# alimV1.net
KiCad netlist of a schematic drawn in EAGLE
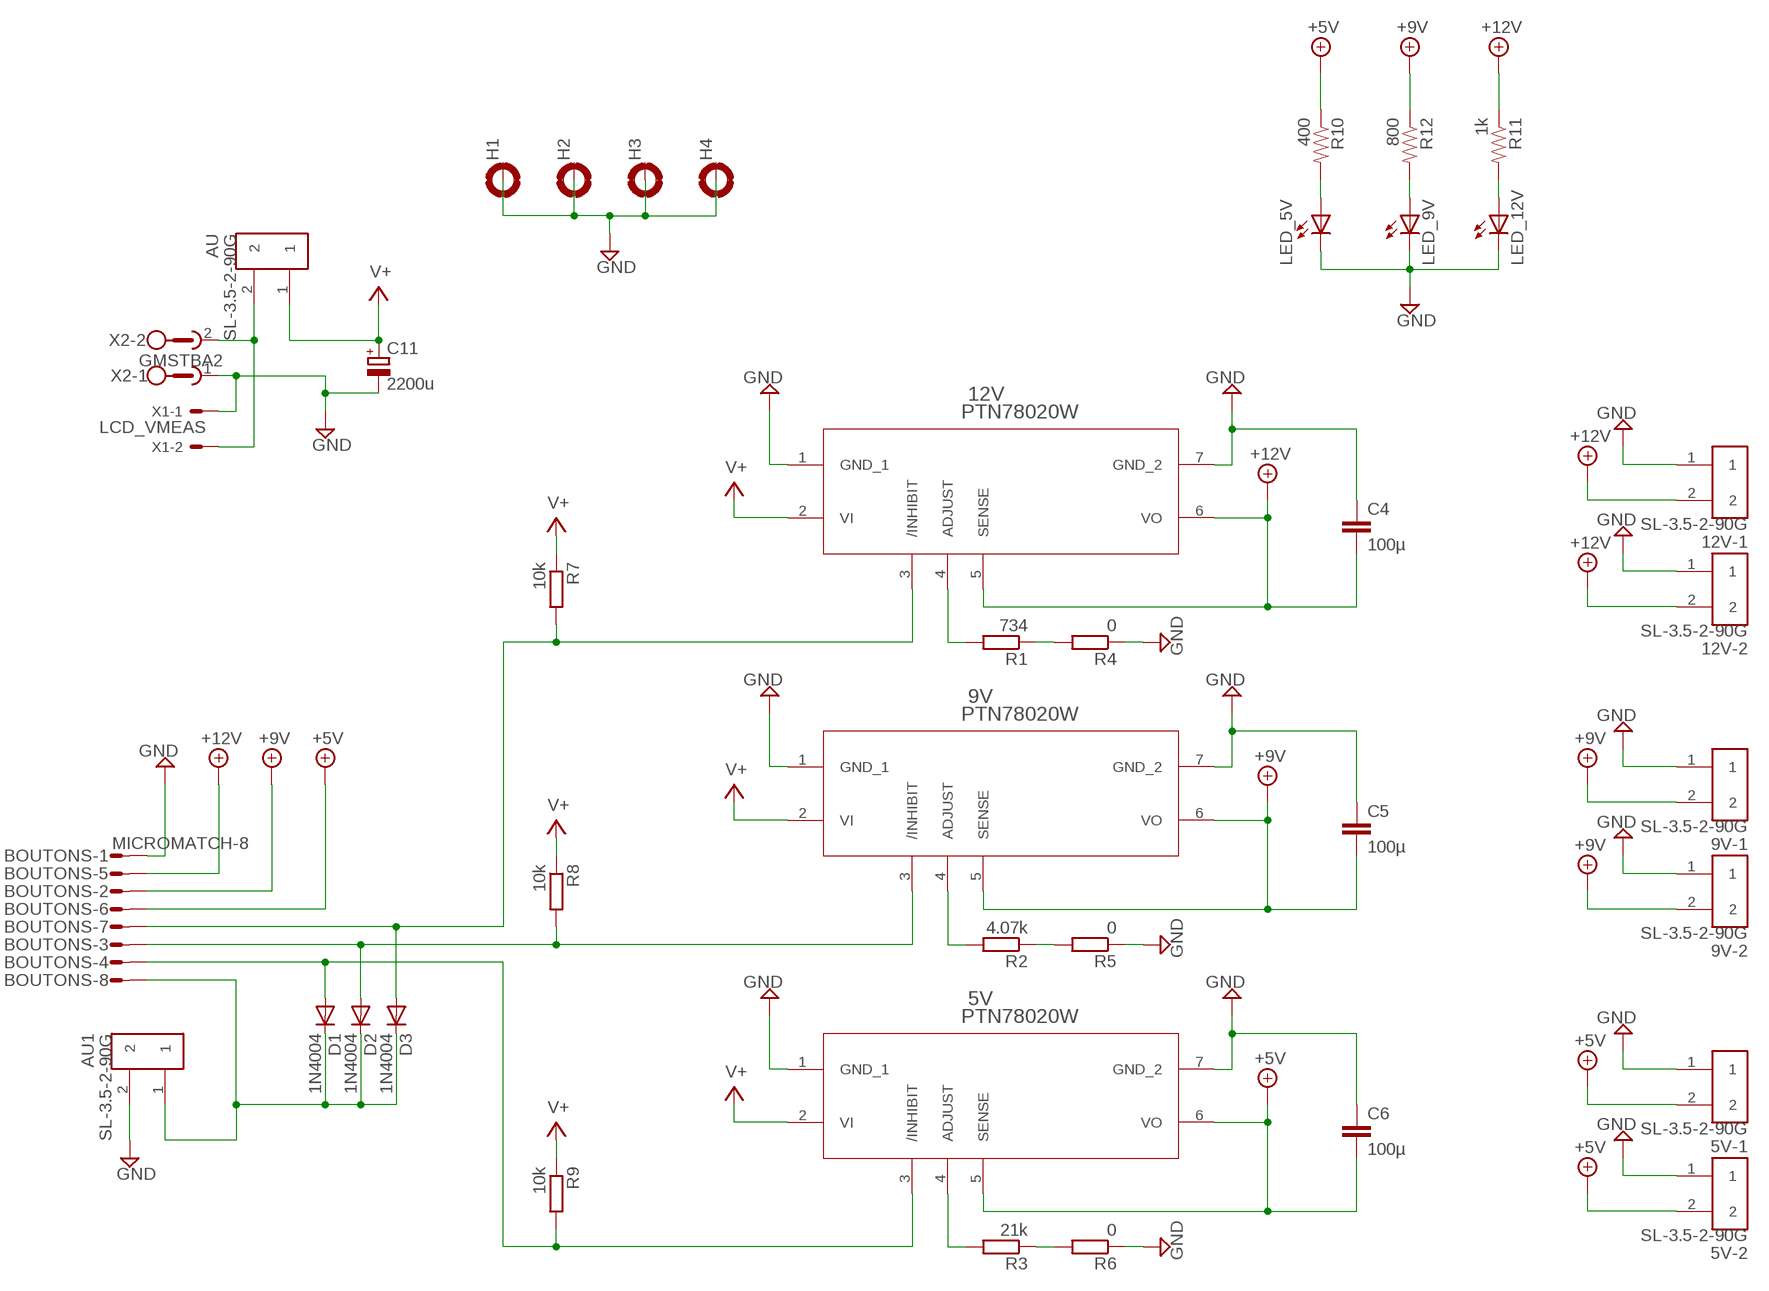
[diagram p0: schematic, sheet 1]

(export (version "E")
  (design (tool "Eeschema 10.0.6"))
  (components
    (comp (ref "5V")
      (value "PTN78020W")
      (footprint "eagle-import:EUK7")
      (libsource (lib "eagle-import") (part "PTN78020W"))
    )
    (comp (ref "5V-1")
      (value "SL-3.5-2-90G")
      (footprint "eagle-import:SL-3.5-2-90G")
      (libsource (lib "eagle-import") (part "SL-3.5-2-90G"))
    )
    (comp (ref "5V-2")
      (value "SL-3.5-2-90G")
      (footprint "eagle-import:SL-3.5-2-90G")
      (libsource (lib "eagle-import") (part "SL-3.5-2-90G"))
    )
    (comp (ref "9V")
      (value "PTN78020W")
      (footprint "eagle-import:EUK7")
      (libsource (lib "eagle-import") (part "PTN78020W"))
    )
    (comp (ref "9V-1")
      (value "SL-3.5-2-90G")
      (footprint "eagle-import:SL-3.5-2-90G")
      (libsource (lib "eagle-import") (part "SL-3.5-2-90G"))
    )
    (comp (ref "9V-2")
      (value "SL-3.5-2-90G")
      (footprint "eagle-import:SL-3.5-2-90G")
      (libsource (lib "eagle-import") (part "SL-3.5-2-90G"))
    )
    (comp (ref "12V")
      (value "PTN78020W")
      (footprint "eagle-import:EUK7")
      (libsource (lib "eagle-import") (part "PTN78020W"))
    )
    (comp (ref "12V-1")
      (value "SL-3.5-2-90G")
      (footprint "eagle-import:SL-3.5-2-90G")
      (libsource (lib "eagle-import") (part "SL-3.5-2-90G"))
    )
    (comp (ref "12V-2")
      (value "SL-3.5-2-90G")
      (footprint "eagle-import:SL-3.5-2-90G")
      (libsource (lib "eagle-import") (part "SL-3.5-2-90G"))
    )
    (comp (ref "AU")
      (value "SL-3.5-2-90G")
      (footprint "eagle-import:SL-3.5-2-90G")
      (libsource (lib "eagle-import") (part "SL-3.5-2-90G"))
    )
    (comp (ref "AU1")
      (value "SL-3.5-2-90G")
      (footprint "eagle-import:SL-3.5-2-90G")
      (libsource (lib "eagle-import") (part "SL-3.5-2-90G"))
    )
    (comp (ref "BOUTONS")
      (value "MICROMATCH-8")
      (footprint "eagle-import:MICROMATCH-8")
      (fields (field (name "MF") "FARNELL") (field (name "MPN") "7-215464-8"))
      (libsource (lib "eagle-import") (part "MICROMATCH-8"))
    )
    (comp (ref "C4")
      (value "100µ")
      (footprint "eagle-import:C025-025X050")
      (libsource (lib "eagle-import") (part "C-EU025-025X050"))
    )
    (comp (ref "C5")
      (value "100µ")
      (footprint "eagle-import:C025-025X050")
      (libsource (lib "eagle-import") (part "C-EU025-025X050"))
    )
    (comp (ref "C6")
      (value "100µ")
      (footprint "eagle-import:C025-025X050")
      (libsource (lib "eagle-import") (part "C-EU025-025X050"))
    )
    (comp (ref "C11")
      (value "2200u")
      (footprint "eagle-import:TT5D11")
      (libsource (lib "eagle-import") (part "CPOL-EUTT5D11"))
    )
    (comp (ref "D1")
      (value "1N4004")
      (footprint "eagle-import:DO41-10")
      (libsource (lib "eagle-import") (part "1N4004"))
    )
    (comp (ref "D2")
      (value "1N4004")
      (footprint "eagle-import:DO41-10")
      (libsource (lib "eagle-import") (part "1N4004"))
    )
    (comp (ref "D3")
      (value "1N4004")
      (footprint "eagle-import:DO41-10")
      (libsource (lib "eagle-import") (part "1N4004"))
    )
    (comp (ref "H1")
      (value "MOUNT-PAD-ROUND3.2")
      (footprint "eagle-import:3,2-PAD")
      (libsource (lib "eagle-import") (part "MOUNT-PAD-ROUND3.2"))
    )
    (comp (ref "H2")
      (value "MOUNT-PAD-ROUND3.2")
      (footprint "eagle-import:3,2-PAD")
      (libsource (lib "eagle-import") (part "MOUNT-PAD-ROUND3.2"))
    )
    (comp (ref "H3")
      (value "MOUNT-PAD-ROUND3.2")
      (footprint "eagle-import:3,2-PAD")
      (libsource (lib "eagle-import") (part "MOUNT-PAD-ROUND3.2"))
    )
    (comp (ref "H4")
      (value "MOUNT-PAD-ROUND3.2")
      (footprint "eagle-import:3,2-PAD")
      (libsource (lib "eagle-import") (part "MOUNT-PAD-ROUND3.2"))
    )
    (comp (ref "LED_5V")
      (value "LEDCHIPLED_0805")
      (footprint "eagle-import:CHIPLED_0805")
      (libsource (lib "eagle-import") (part "LEDCHIPLED_0805"))
    )
    (comp (ref "LED_9V")
      (value "LEDCHIPLED_0805")
      (footprint "eagle-import:CHIPLED_0805")
      (libsource (lib "eagle-import") (part "LEDCHIPLED_0805"))
    )
    (comp (ref "LED_12V")
      (value "LEDCHIPLED_0805")
      (footprint "eagle-import:CHIPLED_0805")
      (libsource (lib "eagle-import") (part "LEDCHIPLED_0805"))
    )
    (comp (ref "R1")
      (value "734")
      (footprint "eagle-import:R0805")
      (libsource (lib "eagle-import") (part "R-EU_R0805"))
    )
    (comp (ref "R2")
      (value "4.07k")
      (footprint "eagle-import:R0805")
      (libsource (lib "eagle-import") (part "R-EU_R0805"))
    )
    (comp (ref "R3")
      (value "21k")
      (footprint "eagle-import:R0805")
      (libsource (lib "eagle-import") (part "R-EU_R0805"))
    )
    (comp (ref "R4")
      (value "0")
      (footprint "eagle-import:R0805")
      (libsource (lib "eagle-import") (part "R-EU_R0805"))
    )
    (comp (ref "R5")
      (value "0")
      (footprint "eagle-import:R0805")
      (libsource (lib "eagle-import") (part "R-EU_R0805"))
    )
    (comp (ref "R6")
      (value "0")
      (footprint "eagle-import:R0805")
      (libsource (lib "eagle-import") (part "R-EU_R0805"))
    )
    (comp (ref "R7")
      (value "10k")
      (footprint "eagle-import:R0805")
      (libsource (lib "eagle-import") (part "R-EU_R0805"))
    )
    (comp (ref "R8")
      (value "10k")
      (footprint "eagle-import:R0805")
      (libsource (lib "eagle-import") (part "R-EU_R0805"))
    )
    (comp (ref "R9")
      (value "10k")
      (footprint "eagle-import:R0805")
      (libsource (lib "eagle-import") (part "R-EU_R0805"))
    )
    (comp (ref "R10")
      (value "400")
      (footprint "eagle-import:0805")
      (libsource (lib "eagle-import") (part "RESISTOR0805-RES"))
    )
    (comp (ref "R11")
      (value "1k")
      (footprint "eagle-import:0805")
      (libsource (lib "eagle-import") (part "RESISTOR0805-RES"))
    )
    (comp (ref "R12")
      (value "800")
      (footprint "eagle-import:0805")
      (libsource (lib "eagle-import") (part "RESISTOR0805-RES"))
    )
    (comp (ref "X1")
      (value "LCD_VMEAS")
      (footprint "eagle-import:22-23-2021")
      (fields (field (name "MF") "MOLEX") (field (name "MPN") "22-23-2021"))
      (libsource (lib "eagle-import") (part "22-23-2021"))
    )
    (comp (ref "X2")
      (value "GMSTBA2")
      (footprint "eagle-import:GMSTBA2")
      (fields (field (name "MF") "FARNELL") (field (name "MPN") "1757242"))
      (libsource (lib "eagle-import") (part "GMSTBA2"))
    )
  )
  (nets
    (net (code "1") (name "+5V") (class "Default")
      (node (ref "5V") (pin "5") (pinfunction "SENSE_5") (pintype "passive"))
      (node (ref "5V") (pin "6") (pinfunction "VO_6") (pintype "passive"))
      (node (ref "5V-1") (pin "2") (pinfunction "2_2") (pintype "bidirectional"))
      (node (ref "5V-2") (pin "2") (pinfunction "2_2") (pintype "bidirectional"))
      (node (ref "BOUTONS") (pin "6") (pinfunction "S_6") (pintype "passive"))
      (node (ref "C6") (pin "2") (pinfunction "2_2") (pintype "passive"))
      (node (ref "R10") (pin "1") (pinfunction "1_1") (pintype "passive"))
    )
    (net (code "2") (name "+9V") (class "Default")
      (node (ref "9V") (pin "5") (pinfunction "SENSE_5") (pintype "passive"))
      (node (ref "9V") (pin "6") (pinfunction "VO_6") (pintype "passive"))
      (node (ref "9V-1") (pin "2") (pinfunction "2_2") (pintype "bidirectional"))
      (node (ref "9V-2") (pin "2") (pinfunction "2_2") (pintype "bidirectional"))
      (node (ref "BOUTONS") (pin "2") (pinfunction "S_2") (pintype "passive"))
      (node (ref "C5") (pin "2") (pinfunction "2_2") (pintype "passive"))
      (node (ref "R12") (pin "1") (pinfunction "1_1") (pintype "passive"))
    )
    (net (code "3") (name "+12V") (class "Default")
      (node (ref "12V") (pin "5") (pinfunction "SENSE_5") (pintype "passive"))
      (node (ref "12V") (pin "6") (pinfunction "VO_6") (pintype "passive"))
      (node (ref "12V-1") (pin "2") (pinfunction "2_2") (pintype "bidirectional"))
      (node (ref "12V-2") (pin "2") (pinfunction "2_2") (pintype "bidirectional"))
      (node (ref "BOUTONS") (pin "5") (pinfunction "S_5") (pintype "passive"))
      (node (ref "C4") (pin "2") (pinfunction "2_2") (pintype "passive"))
      (node (ref "R11") (pin "1") (pinfunction "1_1") (pintype "passive"))
    )
    (net (code "4") (name "GND") (class "Default")
      (node (ref "12V") (pin "1") (pinfunction "GND_1_1") (pintype "passive"))
      (node (ref "12V") (pin "7") (pinfunction "GND_2_7") (pintype "passive"))
      (node (ref "12V-1") (pin "1") (pinfunction "1_1") (pintype "bidirectional"))
      (node (ref "12V-2") (pin "1") (pinfunction "1_1") (pintype "bidirectional"))
      (node (ref "5V") (pin "1") (pinfunction "GND_1_1") (pintype "passive"))
      (node (ref "5V") (pin "7") (pinfunction "GND_2_7") (pintype "passive"))
      (node (ref "5V-1") (pin "1") (pinfunction "1_1") (pintype "bidirectional"))
      (node (ref "5V-2") (pin "1") (pinfunction "1_1") (pintype "bidirectional"))
      (node (ref "9V") (pin "1") (pinfunction "GND_1_1") (pintype "passive"))
      (node (ref "9V") (pin "7") (pinfunction "GND_2_7") (pintype "passive"))
      (node (ref "9V-1") (pin "1") (pinfunction "1_1") (pintype "bidirectional"))
      (node (ref "9V-2") (pin "1") (pinfunction "1_1") (pintype "bidirectional"))
      (node (ref "AU1") (pin "2") (pinfunction "2_2") (pintype "bidirectional"))
      (node (ref "BOUTONS") (pin "1") (pinfunction "S_1") (pintype "passive"))
      (node (ref "C11") (pin "-") (pinfunction "-_-") (pintype "passive"))
      (node (ref "C4") (pin "1") (pinfunction "1_1") (pintype "passive"))
      (node (ref "C5") (pin "1") (pinfunction "1_1") (pintype "passive"))
      (node (ref "C6") (pin "1") (pinfunction "1_1") (pintype "passive"))
      (node (ref "H1") (pin "B3,2") (pinfunction "MOUNT_B3,2") (pintype "passive"))
      (node (ref "H2") (pin "B3,2") (pinfunction "MOUNT_B3,2") (pintype "passive"))
      (node (ref "H3") (pin "B3,2") (pinfunction "MOUNT_B3,2") (pintype "passive"))
      (node (ref "H4") (pin "B3,2") (pinfunction "MOUNT_B3,2") (pintype "passive"))
      (node (ref "LED_12V") (pin "C") (pinfunction "C_C") (pintype "passive"))
      (node (ref "LED_5V") (pin "C") (pinfunction "C_C") (pintype "passive"))
      (node (ref "LED_9V") (pin "C") (pinfunction "C_C") (pintype "passive"))
      (node (ref "R4") (pin "1") (pinfunction "1_1") (pintype "passive"))
      (node (ref "R5") (pin "1") (pinfunction "1_1") (pintype "passive"))
      (node (ref "R6") (pin "1") (pinfunction "1_1") (pintype "passive"))
      (node (ref "X1") (pin "1") (pinfunction "S_1") (pintype "passive"))
      (node (ref "X2") (pin "1") (pinfunction "1_1") (pintype "passive"))
    )
    (net (code "5") (name "Net-(5V-ADJUST)") (class "Default")
      (node (ref "5V") (pin "4") (pinfunction "ADJUST_4") (pintype "passive"))
      (node (ref "R3") (pin "2") (pinfunction "2_2") (pintype "passive"))
    )
    (net (code "6") (name "Net-(5V-{slash}INHIBIT)") (class "Default")
      (node (ref "5V") (pin "3") (pinfunction "/INHIBIT_3") (pintype "passive"))
      (node (ref "BOUTONS") (pin "4") (pinfunction "S_4") (pintype "passive"))
      (node (ref "D1") (pin "A") (pinfunction "A_A") (pintype "passive"))
      (node (ref "R9") (pin "2") (pinfunction "2_2") (pintype "passive"))
    )
    (net (code "7") (name "Net-(9V-ADJUST)") (class "Default")
      (node (ref "9V") (pin "4") (pinfunction "ADJUST_4") (pintype "passive"))
      (node (ref "R2") (pin "2") (pinfunction "2_2") (pintype "passive"))
    )
    (net (code "8") (name "Net-(9V-{slash}INHIBIT)") (class "Default")
      (node (ref "9V") (pin "3") (pinfunction "/INHIBIT_3") (pintype "passive"))
      (node (ref "BOUTONS") (pin "3") (pinfunction "S_3") (pintype "passive"))
      (node (ref "D2") (pin "A") (pinfunction "A_A") (pintype "passive"))
      (node (ref "R8") (pin "2") (pinfunction "2_2") (pintype "passive"))
    )
    (net (code "9") (name "Net-(12V-ADJUST)") (class "Default")
      (node (ref "12V") (pin "4") (pinfunction "ADJUST_4") (pintype "passive"))
      (node (ref "R1") (pin "2") (pinfunction "2_2") (pintype "passive"))
    )
    (net (code "10") (name "Net-(12V-{slash}INHIBIT)") (class "Default")
      (node (ref "12V") (pin "3") (pinfunction "/INHIBIT_3") (pintype "passive"))
      (node (ref "BOUTONS") (pin "7") (pinfunction "S_7") (pintype "passive"))
      (node (ref "D3") (pin "A") (pinfunction "A_A") (pintype "passive"))
      (node (ref "R7") (pin "2") (pinfunction "2_2") (pintype "passive"))
    )
    (net (code "11") (name "Net-(BOUTONSH-S)") (class "Default")
      (node (ref "AU1") (pin "1") (pinfunction "1_1") (pintype "bidirectional"))
      (node (ref "BOUTONS") (pin "8") (pinfunction "S_8") (pintype "passive"))
      (node (ref "D1") (pin "C") (pinfunction "C_C") (pintype "passive"))
      (node (ref "D2") (pin "C") (pinfunction "C_C") (pintype "passive"))
      (node (ref "D3") (pin "C") (pinfunction "C_C") (pintype "passive"))
    )
    (net (code "12") (name "Net-(LED_5V-PadA)") (class "Default")
      (node (ref "LED_5V") (pin "A") (pinfunction "A_A") (pintype "passive"))
      (node (ref "R10") (pin "2") (pinfunction "2_2") (pintype "passive"))
    )
    (net (code "13") (name "Net-(LED_9V-PadA)") (class "Default")
      (node (ref "LED_9V") (pin "A") (pinfunction "A_A") (pintype "passive"))
      (node (ref "R12") (pin "2") (pinfunction "2_2") (pintype "passive"))
    )
    (net (code "14") (name "Net-(LED_12V-PadA)") (class "Default")
      (node (ref "LED_12V") (pin "A") (pinfunction "A_A") (pintype "passive"))
      (node (ref "R11") (pin "2") (pinfunction "2_2") (pintype "passive"))
    )
    (net (code "15") (name "Net-(R1-Pad1)") (class "Default")
      (node (ref "R1") (pin "1") (pinfunction "1_1") (pintype "passive"))
      (node (ref "R4") (pin "2") (pinfunction "2_2") (pintype "passive"))
    )
    (net (code "16") (name "Net-(R2-Pad1)") (class "Default")
      (node (ref "R2") (pin "1") (pinfunction "1_1") (pintype "passive"))
      (node (ref "R5") (pin "2") (pinfunction "2_2") (pintype "passive"))
    )
    (net (code "17") (name "Net-(R3-Pad1)") (class "Default")
      (node (ref "R3") (pin "1") (pinfunction "1_1") (pintype "passive"))
      (node (ref "R6") (pin "2") (pinfunction "2_2") (pintype "passive"))
    )
    (net (code "18") (name "Net-(X1B-S)") (class "Default")
      (node (ref "AU") (pin "2") (pinfunction "2_2") (pintype "bidirectional"))
      (node (ref "X1") (pin "2") (pinfunction "S_2") (pintype "passive"))
      (node (ref "X2") (pin "2") (pinfunction "1_2") (pintype "passive"))
    )
    (net (code "19") (name "V+") (class "Default")
      (node (ref "12V") (pin "2") (pinfunction "VI_2") (pintype "passive"))
      (node (ref "5V") (pin "2") (pinfunction "VI_2") (pintype "passive"))
      (node (ref "9V") (pin "2") (pinfunction "VI_2") (pintype "passive"))
      (node (ref "AU") (pin "1") (pinfunction "1_1") (pintype "bidirectional"))
      (node (ref "C11") (pin "+") (pinfunction "+_+") (pintype "passive"))
      (node (ref "R7") (pin "1") (pinfunction "1_1") (pintype "passive"))
      (node (ref "R8") (pin "1") (pinfunction "1_1") (pintype "passive"))
      (node (ref "R9") (pin "1") (pinfunction "1_1") (pintype "passive"))
    )
  )
)
